# Lipo-Charger-5V-setup_RevB.net
KiCad netlist of a schematic drawn in EAGLE
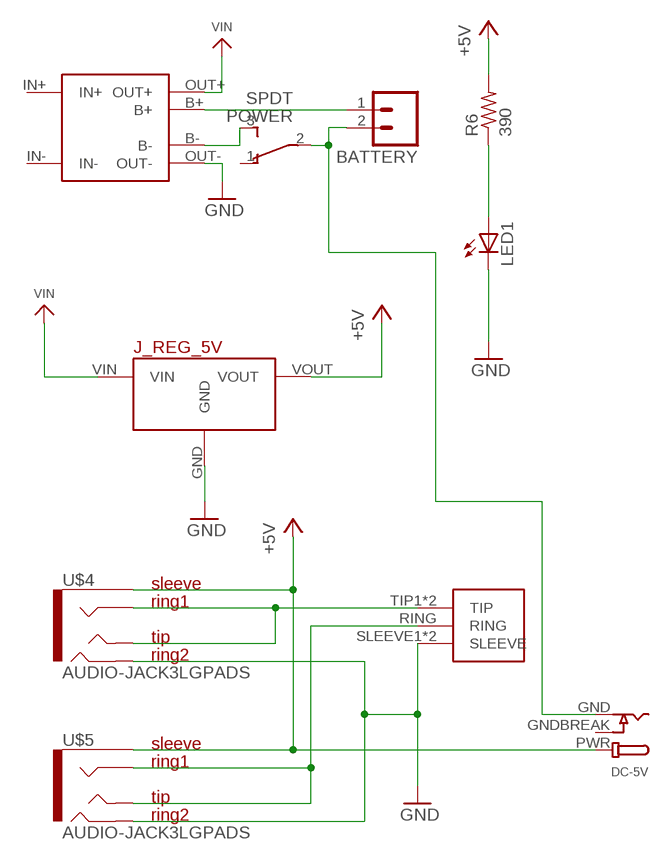
[diagram p0: schematic, sheet 1]

(export (version "E")
  (design (tool "Eeschema 10.0.6"))
  (components
    (comp (ref "AUDIO_OUT")
      (value "1/8\"-F-STEREO-PCB")
      (footprint "eagle-import:1_8_-F-STEREO-PCB")
      (libsource (lib "eagle-import") (part "1/8{dblquote}-F-STEREO-PCB"))
    )
    (comp (ref "BATTERY")
      (value "M02LOCK")
      (footprint "eagle-import:1X02_LOCK")
      (libsource (lib "eagle-import") (part "M02LOCK"))
    )
    (comp (ref "DC-5V")
      (value "DCBARRELPTH")
      (footprint "eagle-import:DCJACK_2MM_PTH")
      (libsource (lib "eagle-import") (part "DCBARRELPTH"))
    )
    (comp (ref "J_REG_5V")
      (value "POLOLU_VOLTAGE_REGULATORS_3PIN")
      (footprint "eagle-import:POLOLU_5V-12V_STEPUP_U3V12F5-U3V12F12")
      (libsource (lib "eagle-import") (part "POLOLU_VOLTAGE_REGULATORS_3PIN"))
    )
    (comp (ref "LED1")
      (value "LED3MM")
      (footprint "eagle-import:LED3MM")
      (libsource (lib "eagle-import") (part "LED3MM"))
    )
    (comp (ref "POWER")
      (value "SPDT")
      (footprint "eagle-import:SWITCH_SPDT-TE-CONNECT")
      (libsource (lib "eagle-import") (part "SWITCH_SPDTTE-CONNECT"))
    )
    (comp (ref "R6")
      (value "390")
      (footprint "eagle-import:0204_7")
      (libsource (lib "eagle-import") (part "R-US_0204/7"))
    )
    (comp (ref "U$4")
      (value "AUDIO-JACK3LGPADS")
      (footprint "eagle-import:AUDIO-JACK-TRRS-SMD")
      (libsource (lib "eagle-import") (part "AUDIO-JACK3LGPADS"))
    )
    (comp (ref "U$5")
      (value "AUDIO-JACK3LGPADS")
      (footprint "eagle-import:AUDIO-JACK-TRRS-SMD")
      (libsource (lib "eagle-import") (part "AUDIO-JACK3LGPADS"))
    )
    (comp (ref "USB-LIPO-CHARGER")
      (value "TP4056-MODULE")
      (footprint "eagle-import:TP4056-LITHIUM-PROTECTED-MODULE")
      (libsource (lib "eagle-import") (part "TP4056-MODULE"))
    )
  )
  (nets
    (net (code "1") (name "+5V") (class "Default")
      (node (ref "DC-5V") (pin "PWR") (pinfunction "PWR_PWR") (pintype "power_in"))
      (node (ref "J_REG_5V") (pin "VOUT") (pinfunction "VOUT_VOUT") (pintype "bidirectional"))
      (node (ref "R6") (pin "2") (pinfunction "2_2") (pintype "passive"))
      (node (ref "U$4") (pin "EARTH") (pinfunction "EARTH_EARTH") (pintype "bidirectional"))
      (node (ref "U$5") (pin "EARTH") (pinfunction "EARTH_EARTH") (pintype "bidirectional"))
    )
    (net (code "2") (name "/GNDBREAK") (class "Default")
      (node (ref "DC-5V") (pin "GNDBREAK") (pinfunction "GNDBREAK_GNDBREAK") (pintype "power_in"))
    )
    (net (code "3") (name "/IN+") (class "Default")
      (node (ref "USB-LIPO-CHARGER") (pin "IN+") (pinfunction "IN+_IN+") (pintype "power_in"))
    )
    (net (code "4") (name "/IN-") (class "Default")
      (node (ref "USB-LIPO-CHARGER") (pin "IN-") (pinfunction "IN-_IN-") (pintype "power_in"))
    )
    (net (code "5") (name "GND") (class "Default")
      (node (ref "AUDIO_OUT") (pin "SLEEVE1") (pinfunction "SLEEVE_SLEEVE1") (pintype "bidirectional"))
      (node (ref "AUDIO_OUT") (pin "SLEEVE2") (pinfunction "SLEEVE_SLEEVE2") (pintype "bidirectional"))
      (node (ref "J_REG_5V") (pin "GND") (pinfunction "GND_GND") (pintype "bidirectional"))
      (node (ref "LED1") (pin "K") (pinfunction "C_K") (pintype "passive"))
      (node (ref "U$4") (pin "RING2") (pinfunction "RING2_RING2") (pintype "bidirectional"))
      (node (ref "U$5") (pin "RING2") (pinfunction "RING2_RING2") (pintype "bidirectional"))
      (node (ref "USB-LIPO-CHARGER") (pin "OUT-") (pinfunction "OUT-_OUT-") (pintype "power_in"))
    )
    (net (code "6") (name "Net-(AUDIO_OUT-PadRING)") (class "Default")
      (node (ref "AUDIO_OUT") (pin "RING") (pinfunction "RING_RING") (pintype "bidirectional"))
      (node (ref "U$5") (pin "RING1") (pinfunction "RING1_RING1") (pintype "bidirectional"))
      (node (ref "U$5") (pin "TIP") (pinfunction "TIP_TIP") (pintype "bidirectional"))
    )
    (net (code "7") (name "Net-(AUDIO_OUT-TIP-PadTIP1)") (class "Default")
      (node (ref "AUDIO_OUT") (pin "TIP1") (pinfunction "TIP_TIP1") (pintype "bidirectional"))
      (node (ref "AUDIO_OUT") (pin "TIP2") (pinfunction "TIP_TIP2") (pintype "bidirectional"))
      (node (ref "U$4") (pin "RING1") (pinfunction "RING1_RING1") (pintype "bidirectional"))
      (node (ref "U$4") (pin "TIP") (pinfunction "TIP_TIP") (pintype "bidirectional"))
    )
    (net (code "8") (name "Net-(BATTERY-Pad1)") (class "Default")
      (node (ref "BATTERY") (pin "1") (pinfunction "1_1") (pintype "passive"))
      (node (ref "USB-LIPO-CHARGER") (pin "B+") (pinfunction "B+_B+") (pintype "power_in"))
    )
    (net (code "9") (name "Net-(BATTERY-Pad2)") (class "Default")
      (node (ref "BATTERY") (pin "2") (pinfunction "2_2") (pintype "passive"))
      (node (ref "DC-5V") (pin "GND") (pinfunction "GND_GND") (pintype "power_in"))
      (node (ref "POWER") (pin "2") (pinfunction "2_2") (pintype "passive"))
    )
    (net (code "10") (name "Net-(LED1-PadA)") (class "Default")
      (node (ref "LED1") (pin "A") (pinfunction "A_A") (pintype "passive"))
      (node (ref "R6") (pin "1") (pinfunction "1_1") (pintype "passive"))
    )
    (net (code "11") (name "Net-(POWER-Pad3)") (class "Default")
      (node (ref "POWER") (pin "3") (pinfunction "3_3") (pintype "passive"))
      (node (ref "USB-LIPO-CHARGER") (pin "B-") (pinfunction "B-_B-") (pintype "power_in"))
    )
    (net (code "12") (name "VIN") (class "Default")
      (node (ref "J_REG_5V") (pin "VIN") (pinfunction "VIN_VIN") (pintype "bidirectional"))
      (node (ref "USB-LIPO-CHARGER") (pin "OUT+") (pinfunction "OUT+_OUT+") (pintype "power_in"))
    )
    (net (code "13") (name "unconnected-(POWER-Pad1)") (class "Default")
      (node (ref "POWER") (pin "1") (pinfunction "1_1") (pintype "passive"))
    )
  )
)
